# UTX-2022F010.net
KiCad netlist of a schematic drawn in EAGLE
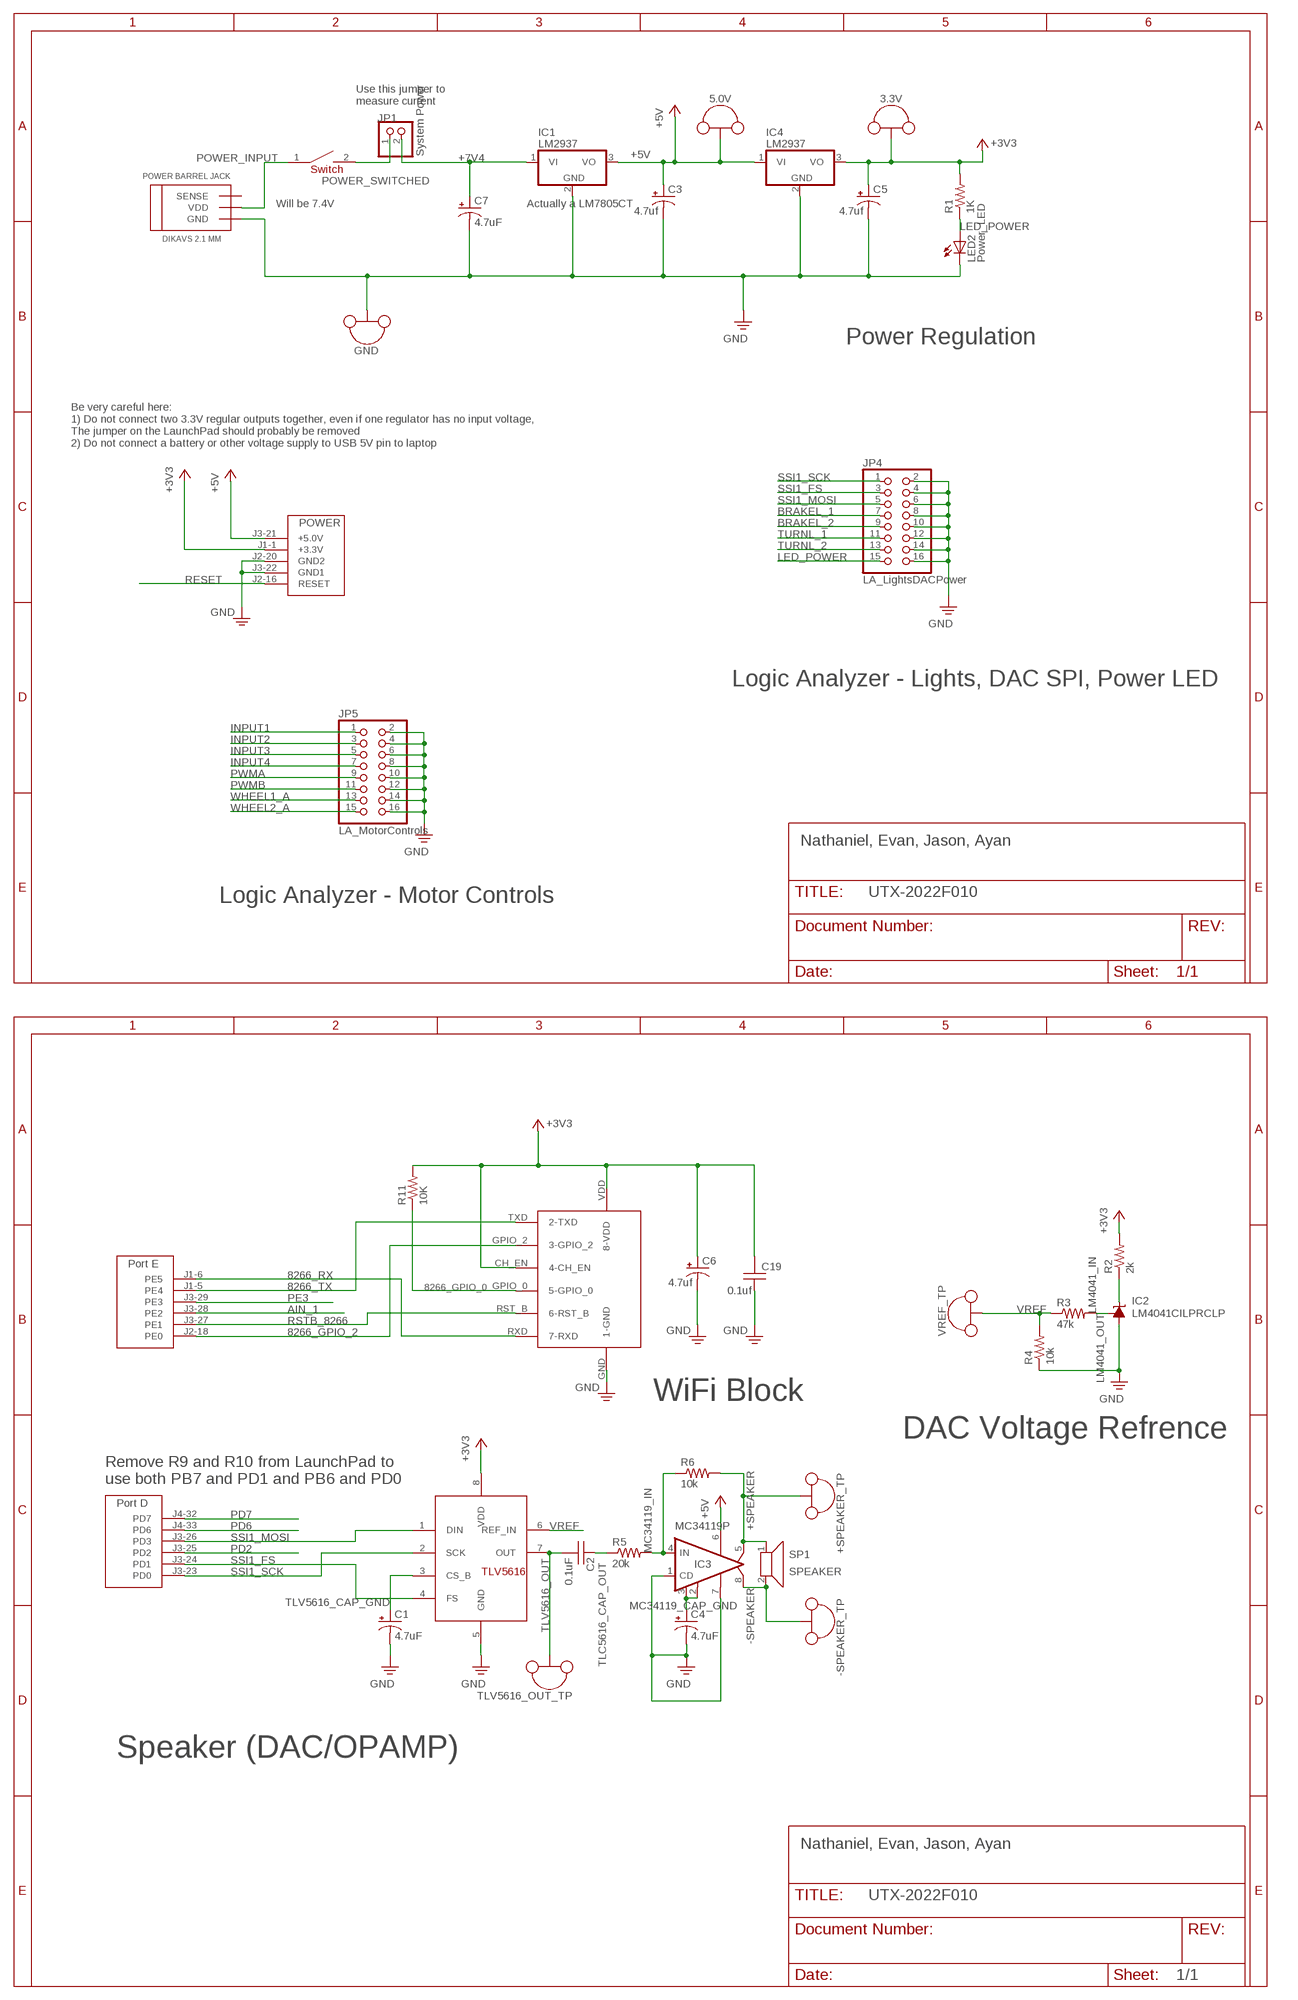
[diagram p0: schematic, sheet 1, part 1 of 2]
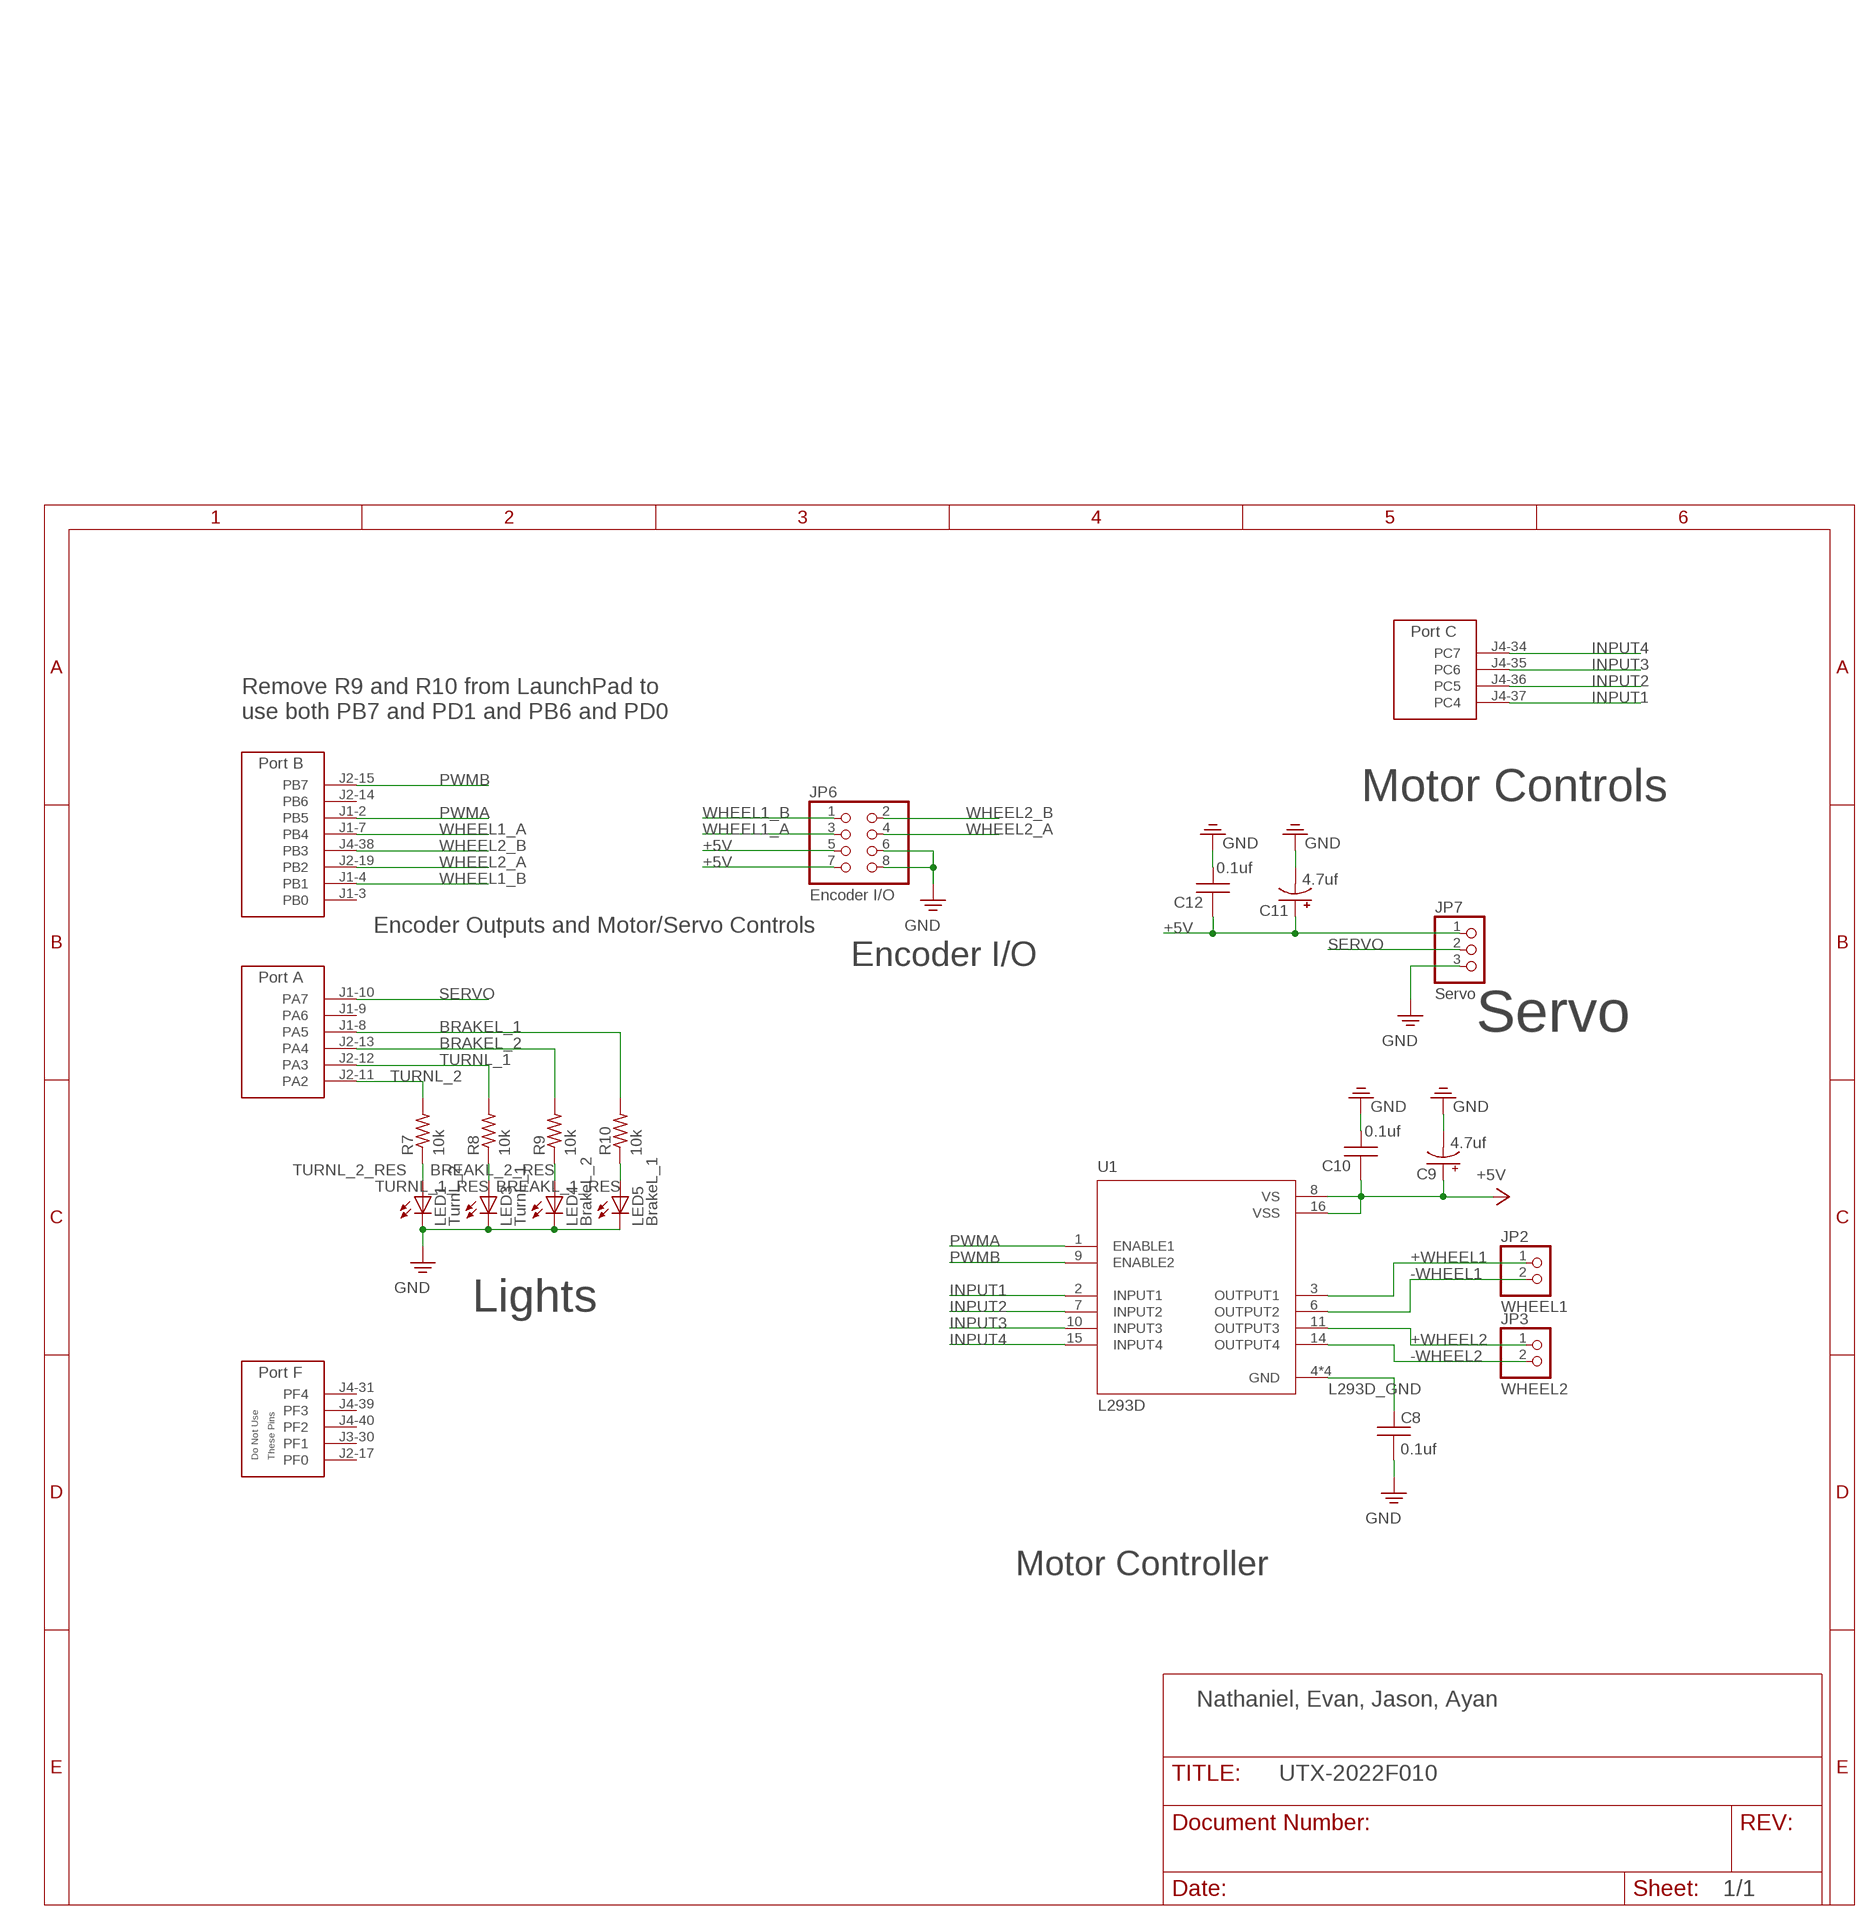
[diagram p1: schematic, sheet 1, part 2 of 2]

(export (version "E")
  (design (tool "Eeschema 10.0.6"))
  (components
    (comp (ref "+SPEAKER_TP")
      (value "TP_LOOP")
      (footprint "eagle-import:TP_LOOP")
      (libsource (lib "eagle-import") (part "TP_LOOP"))
    )
    (comp (ref "-SPEAKER_TP")
      (value "TP_LOOP")
      (footprint "eagle-import:TP_LOOP")
      (libsource (lib "eagle-import") (part "TP_LOOP"))
    )
    (comp (ref "3.3V")
      (value "TP_LOOP")
      (footprint "eagle-import:TP_LOOP")
      (libsource (lib "eagle-import") (part "TP_LOOP"))
    )
    (comp (ref "5.0V")
      (value "TP_LOOP")
      (footprint "eagle-import:TP_LOOP")
      (libsource (lib "eagle-import") (part "TP_LOOP"))
    )
    (comp (ref "C1")
      (value "4.7uF")
      (footprint "eagle-import:CAP200MILPOLARIZED")
      (libsource (lib "eagle-import") (part "CAPACITOR_POLARIZEDE5-6"))
    )
    (comp (ref "C2")
      (value "0.1uF")
      (footprint "eagle-import:CAP100MIL")
      (libsource (lib "eagle-import") (part "CAPACITOR025-024X044"))
    )
    (comp (ref "C3")
      (value "4.7uf")
      (footprint "eagle-import:CAP200MILPOLARIZED")
      (libsource (lib "eagle-import") (part "CAPACITOR_POLARIZEDE5-6"))
    )
    (comp (ref "C4")
      (value "4.7uF")
      (footprint "eagle-import:CAP200MILPOLARIZED")
      (libsource (lib "eagle-import") (part "CAPACITOR_POLARIZEDE5-6"))
    )
    (comp (ref "C5")
      (value "4.7uf")
      (footprint "eagle-import:CAP200MILPOLARIZED")
      (libsource (lib "eagle-import") (part "CAPACITOR_POLARIZEDE5-6"))
    )
    (comp (ref "C6")
      (value "4.7uf")
      (footprint "eagle-import:CAP200MILPOLARIZED")
      (libsource (lib "eagle-import") (part "CAPACITOR_POLARIZEDE5-6"))
    )
    (comp (ref "C7")
      (value "4.7uF")
      (footprint "eagle-import:CAP200MILPOLARIZED")
      (libsource (lib "eagle-import") (part "CAPACITOR_POLARIZEDE5-6"))
    )
    (comp (ref "C8")
      (value "0.1uf")
      (footprint "eagle-import:CAP100MIL")
      (libsource (lib "eagle-import") (part "CAPACITOR025-024X044"))
    )
    (comp (ref "C9")
      (value "4.7uf")
      (footprint "eagle-import:CAP200MILPOLARIZED")
      (libsource (lib "eagle-import") (part "CAPACITOR_POLARIZEDE5-6"))
    )
    (comp (ref "C10")
      (value "0.1uf")
      (footprint "eagle-import:CAP200MIL")
      (libsource (lib "eagle-import") (part "CAPACITOR050-024X044"))
    )
    (comp (ref "C11")
      (value "4.7uf")
      (footprint "eagle-import:CAP200MILPOLARIZED")
      (libsource (lib "eagle-import") (part "CAPACITOR_POLARIZEDE5-6"))
    )
    (comp (ref "C12")
      (value "0.1uf")
      (footprint "eagle-import:CAP200MIL")
      (libsource (lib "eagle-import") (part "CAPACITOR050-024X044"))
    )
    (comp (ref "C19")
      (value "0.1uf")
      (footprint "eagle-import:CAP200MIL")
      (libsource (lib "eagle-import") (part "CAPACITOR050-024X044"))
    )
    (comp (ref "GND")
      (value "TP_LOOP")
      (footprint "eagle-import:TP_LOOP")
      (libsource (lib "eagle-import") (part "TP_LOOP"))
    )
    (comp (ref "IC1")
      (value "LM2937")
      (footprint "eagle-import:TO220")
      (libsource (lib "eagle-import") (part "LM2937"))
    )
    (comp (ref "IC2")
      (value "LM4041CILPRCLP")
      (footprint "eagle-import:LP_O-PBCY-W3")
      (fields (field (name "MPN") "LM4041CILP"))
      (libsource (lib "eagle-import") (part "LM4041CILPRLPC"))
    )
    (comp (ref "IC3")
      (value "MC34119P")
      (footprint "eagle-import:DIL08")
      (libsource (lib "eagle-import") (part "MC34119P"))
    )
    (comp (ref "IC4")
      (value "LM2937")
      (footprint "eagle-import:TO220")
      (libsource (lib "eagle-import") (part "LM2937"))
    )
    (comp (ref "JP1")
      (value "System Power")
      (footprint "eagle-import:1X02")
      (libsource (lib "eagle-import") (part "PINHD-1X2"))
    )
    (comp (ref "JP2")
      (value "WHEEL1")
      (footprint "eagle-import:1X02")
      (libsource (lib "eagle-import") (part "PINHD-1X2"))
    )
    (comp (ref "JP3")
      (value "WHEEL2")
      (footprint "eagle-import:1X02")
      (libsource (lib "eagle-import") (part "PINHD-1X2"))
    )
    (comp (ref "JP4")
      (value "LA_LightsDACPower")
      (footprint "eagle-import:2X08")
      (libsource (lib "eagle-import") (part "PINHD-2X8"))
    )
    (comp (ref "JP5")
      (value "LA_MotorControls")
      (footprint "eagle-import:2X08")
      (libsource (lib "eagle-import") (part "PINHD-2X8"))
    )
    (comp (ref "JP6")
      (value "Encoder I/O")
      (footprint "eagle-import:2X04")
      (libsource (lib "eagle-import") (part "PINHD-2X4"))
    )
    (comp (ref "JP7")
      (value "Servo")
      (footprint "eagle-import:1X03")
      (libsource (lib "eagle-import") (part "PINHD-1X3"))
    )
    (comp (ref "LED1")
      (value "TurnL_2")
      (footprint "eagle-import:LED3MM")
      (libsource (lib "eagle-import") (part "LED3MM"))
    )
    (comp (ref "LED2")
      (value "Power_LED")
      (footprint "eagle-import:LED3MM")
      (libsource (lib "eagle-import") (part "LED3MM"))
    )
    (comp (ref "LED3")
      (value "TurnL_1")
      (footprint "eagle-import:LED3MM")
      (libsource (lib "eagle-import") (part "LED3MM"))
    )
    (comp (ref "LED4")
      (value "BrakeL_2")
      (footprint "eagle-import:LED3MM")
      (libsource (lib "eagle-import") (part "LED3MM"))
    )
    (comp (ref "LED5")
      (value "BrakeL_1")
      (footprint "eagle-import:LED3MM")
      (libsource (lib "eagle-import") (part "LED3MM"))
    )
    (comp (ref "R1")
      (value "1K")
      (footprint "eagle-import:RES200MIL")
      (libsource (lib "eagle-import") (part "RESISTOR0204/5"))
    )
    (comp (ref "R2")
      (value "2k")
      (footprint "eagle-import:RES200MIL")
      (libsource (lib "eagle-import") (part "RESISTOR0204/5"))
    )
    (comp (ref "R3")
      (value "47k")
      (footprint "eagle-import:RES200MIL")
      (libsource (lib "eagle-import") (part "RESISTOR0204/5"))
    )
    (comp (ref "R4")
      (value "10k")
      (footprint "eagle-import:RES200MIL")
      (libsource (lib "eagle-import") (part "RESISTOR0204/5"))
    )
    (comp (ref "R5")
      (value "20k")
      (footprint "eagle-import:RES200MIL")
      (libsource (lib "eagle-import") (part "RESISTOR0204/5"))
    )
    (comp (ref "R6")
      (value "10k")
      (footprint "eagle-import:RES200MIL")
      (libsource (lib "eagle-import") (part "RESISTOR0204/5"))
    )
    (comp (ref "R7")
      (value "10k")
      (footprint "eagle-import:RES200MIL")
      (libsource (lib "eagle-import") (part "RESISTOR0204/5"))
    )
    (comp (ref "R8")
      (value "10k")
      (footprint "eagle-import:RES200MIL")
      (libsource (lib "eagle-import") (part "RESISTOR0204/5"))
    )
    (comp (ref "R9")
      (value "10k")
      (footprint "eagle-import:RES200MIL")
      (libsource (lib "eagle-import") (part "RESISTOR0204/5"))
    )
    (comp (ref "R10")
      (value "10k")
      (footprint "eagle-import:RES200MIL")
      (libsource (lib "eagle-import") (part "RESISTOR0204/5"))
    )
    (comp (ref "R11")
      (value "10K")
      (footprint "eagle-import:RES300MIL")
      (libsource (lib "eagle-import") (part "RESISTOR0204/7"))
    )
    (comp (ref "SP1")
      (value "SPEAKER")
      (footprint "eagle-import:1X02")
      (libsource (lib "eagle-import") (part "SPEAKER"))
    )
    (comp (ref "TLV5616_OUT_TP")
      (value "TP_LOOP")
      (footprint "eagle-import:TP_LOOP")
      (libsource (lib "eagle-import") (part "TP_LOOP"))
    )
    (comp (ref "U$1")
      (value "TLV5616")
      (footprint "eagle-import:DIL08")
      (libsource (lib "eagle-import") (part "TLV5616"))
    )
    (comp (ref "U$2")
      (value "TM4C_BP")
      (footprint "eagle-import:TM4C_BOOSTER_PACK")
      (libsource (lib "eagle-import") (part "TM4C_BP"))
    )
    (comp (ref "U$3")
      (value "ESP_8266")
      (footprint "eagle-import:ESP8266")
      (libsource (lib "eagle-import") (part "ESP_8266"))
    )
    (comp (ref "U$4")
      (value "2.1MM_BARREL_JACK")
      (footprint "eagle-import:2.1M_BARREL_JACK")
      (libsource (lib "eagle-import") (part "2.1MM_BARREL_JACK"))
    )
    (comp (ref "U$6")
      (value "SW_POWER_100MIL")
      (footprint "eagle-import:SW_POWER")
      (libsource (lib "eagle-import") (part "SW_POWER_100MIL"))
    )
    (comp (ref "U1")
      (value "L293D")
      (footprint "eagle-import:DIP880W50P254L2000H510Q16")
      (fields (field (name "MF") "STMicroelectronics"))
      (libsource (lib "eagle-import") (part "L293D"))
    )
    (comp (ref "VREF_TP")
      (value "TP_LOOP")
      (footprint "eagle-import:TP_LOOP")
      (libsource (lib "eagle-import") (part "TP_LOOP"))
    )
  )
  (nets
    (net (code "1") (name "+3V3") (class "Default")
      (node (ref "3.3V") (pin "P$1") (pinfunction "TP_P$1") (pintype "bidirectional"))
      (node (ref "3.3V") (pin "P$2") (pinfunction "TP_P$2") (pintype "bidirectional"))
      (node (ref "C19") (pin "2") (pinfunction "2_2") (pintype "passive"))
      (node (ref "C5") (pin "+") (pinfunction "+_+") (pintype "passive"))
      (node (ref "C6") (pin "+") (pinfunction "+_+") (pintype "passive"))
      (node (ref "IC4") (pin "3") (pinfunction "VO_3") (pintype "passive"))
      (node (ref "R1") (pin "2") (pinfunction "2_2") (pintype "passive"))
      (node (ref "R11") (pin "2") (pinfunction "2_2") (pintype "passive"))
      (node (ref "R2") (pin "2") (pinfunction "2_2") (pintype "passive"))
      (node (ref "U$1") (pin "8") (pinfunction "VDD_8") (pintype "bidirectional"))
      (node (ref "U$2") (pin "J1-1") (pinfunction "+3.3V_J1-1") (pintype "bidirectional"))
      (node (ref "U$3") (pin "CH_EN") (pinfunction "4-CH_EN_CH_EN") (pintype "bidirectional"))
      (node (ref "U$3") (pin "VDD") (pinfunction "8-VDD_VDD") (pintype "bidirectional"))
    )
    (net (code "2") (name "+5V") (class "Default")
      (node (ref "5.0V") (pin "P$1") (pinfunction "TP_P$1") (pintype "bidirectional"))
      (node (ref "5.0V") (pin "P$2") (pinfunction "TP_P$2") (pintype "bidirectional"))
      (node (ref "C10") (pin "2") (pinfunction "2_2") (pintype "passive"))
      (node (ref "C11") (pin "+") (pinfunction "+_+") (pintype "passive"))
      (node (ref "C12") (pin "2") (pinfunction "2_2") (pintype "passive"))
      (node (ref "C3") (pin "+") (pinfunction "+_+") (pintype "passive"))
      (node (ref "C9") (pin "+") (pinfunction "+_+") (pintype "passive"))
      (node (ref "IC1") (pin "3") (pinfunction "VO_3") (pintype "passive"))
      (node (ref "IC3") (pin "6") (pinfunction "VCC_6") (pintype "power_in"))
      (node (ref "IC4") (pin "1") (pinfunction "VI_1") (pintype "input"))
      (node (ref "JP6") (pin "5") (pinfunction "5_5") (pintype "passive"))
      (node (ref "JP6") (pin "7") (pinfunction "7_7") (pintype "passive"))
      (node (ref "JP7") (pin "1") (pinfunction "1_1") (pintype "passive"))
      (node (ref "U$2") (pin "J3-21") (pinfunction "+5.0V_J3-21") (pintype "bidirectional"))
      (node (ref "U1") (pin "16") (pinfunction "VSS_16") (pintype "power_in"))
      (node (ref "U1") (pin "8") (pinfunction "VS_8") (pintype "power_in"))
    )
    (net (code "3") (name "/+7V4") (class "Default")
      (node (ref "C7") (pin "+") (pinfunction "+_+") (pintype "passive"))
      (node (ref "IC1") (pin "1") (pinfunction "VI_1") (pintype "input"))
      (node (ref "JP1") (pin "2") (pinfunction "2_2") (pintype "passive"))
    )
    (net (code "4") (name "/+SPEAKER") (class "Default")
      (node (ref "+SPEAKER_TP") (pin "P$1") (pinfunction "TP_P$1") (pintype "bidirectional"))
      (node (ref "+SPEAKER_TP") (pin "P$2") (pinfunction "TP_P$2") (pintype "bidirectional"))
      (node (ref "IC3") (pin "5") (pinfunction "VO1_5") (pintype "output"))
      (node (ref "R6") (pin "2") (pinfunction "2_2") (pintype "passive"))
      (node (ref "SP1") (pin "1") (pinfunction "1_1") (pintype "passive"))
    )
    (net (code "5") (name "/+WHEEL1") (class "Default")
      (node (ref "JP2") (pin "1") (pinfunction "1_1") (pintype "passive"))
      (node (ref "U1") (pin "3") (pinfunction "OUTPUT1_3") (pintype "output"))
    )
    (net (code "6") (name "/+WHEEL2") (class "Default")
      (node (ref "JP3") (pin "1") (pinfunction "1_1") (pintype "passive"))
      (node (ref "U1") (pin "11") (pinfunction "OUTPUT3_11") (pintype "output"))
    )
    (net (code "7") (name "/-SPEAKER") (class "Default")
      (node (ref "-SPEAKER_TP") (pin "P$1") (pinfunction "TP_P$1") (pintype "bidirectional"))
      (node (ref "-SPEAKER_TP") (pin "P$2") (pinfunction "TP_P$2") (pintype "bidirectional"))
      (node (ref "IC3") (pin "8") (pinfunction "VO2_8") (pintype "output"))
      (node (ref "SP1") (pin "2") (pinfunction "2_2") (pintype "passive"))
    )
    (net (code "8") (name "/-WHEEL1") (class "Default")
      (node (ref "JP2") (pin "2") (pinfunction "2_2") (pintype "passive"))
      (node (ref "U1") (pin "6") (pinfunction "OUTPUT2_6") (pintype "output"))
    )
    (net (code "9") (name "/-WHEEL2") (class "Default")
      (node (ref "JP3") (pin "2") (pinfunction "2_2") (pintype "passive"))
      (node (ref "U1") (pin "14") (pinfunction "OUTPUT4_14") (pintype "output"))
    )
    (net (code "10") (name "/8266_GPIO_0") (class "Default")
      (node (ref "R11") (pin "1") (pinfunction "1_1") (pintype "passive"))
      (node (ref "U$3") (pin "GPIO_0") (pinfunction "5-GPIO_0_GPIO_0") (pintype "bidirectional"))
    )
    (net (code "11") (name "/8266_GPIO_2") (class "Default")
      (node (ref "U$2") (pin "J2-18") (pinfunction "PE0_J2-18") (pintype "bidirectional"))
      (node (ref "U$3") (pin "GPIO_2") (pinfunction "3-GPIO_2_GPIO_2") (pintype "bidirectional"))
    )
    (net (code "12") (name "/8266_RX") (class "Default")
      (node (ref "U$2") (pin "J1-6") (pinfunction "PE5_J1-6") (pintype "bidirectional"))
      (node (ref "U$3") (pin "RXD") (pinfunction "7-RXD_RXD") (pintype "bidirectional"))
    )
    (net (code "13") (name "/8266_TX") (class "Default")
      (node (ref "U$2") (pin "J1-5") (pinfunction "PE4_J1-5") (pintype "bidirectional"))
      (node (ref "U$3") (pin "TXD") (pinfunction "2-TXD_TXD") (pintype "bidirectional"))
    )
    (net (code "14") (name "/AIN_1") (class "Default")
      (node (ref "U$2") (pin "J3-28") (pinfunction "PE2_J3-28") (pintype "bidirectional"))
    )
    (net (code "15") (name "/BRAKEL_1") (class "Default")
      (node (ref "JP4") (pin "7") (pinfunction "7_7") (pintype "passive"))
      (node (ref "R10") (pin "2") (pinfunction "2_2") (pintype "passive"))
      (node (ref "U$2") (pin "J1-8") (pinfunction "PA5_J1-8") (pintype "bidirectional"))
    )
    (net (code "16") (name "/BRAKEL_2") (class "Default")
      (node (ref "JP4") (pin "9") (pinfunction "9_9") (pintype "passive"))
      (node (ref "R9") (pin "2") (pinfunction "2_2") (pintype "passive"))
      (node (ref "U$2") (pin "J2-13") (pinfunction "PA4_J2-13") (pintype "bidirectional"))
    )
    (net (code "17") (name "/BREAKL_1_RES") (class "Default")
      (node (ref "LED5") (pin "A") (pinfunction "A_A") (pintype "passive"))
      (node (ref "R10") (pin "1") (pinfunction "1_1") (pintype "passive"))
    )
    (net (code "18") (name "/BREAKL_2_RES") (class "Default")
      (node (ref "LED4") (pin "A") (pinfunction "A_A") (pintype "passive"))
      (node (ref "R9") (pin "1") (pinfunction "1_1") (pintype "passive"))
    )
    (net (code "19") (name "/INPUT1") (class "Default")
      (node (ref "JP5") (pin "1") (pinfunction "1_1") (pintype "passive"))
      (node (ref "U$2") (pin "J4-37") (pinfunction "PC4_J4-37") (pintype "bidirectional"))
      (node (ref "U1") (pin "2") (pinfunction "INPUT1_2") (pintype "input"))
    )
    (net (code "20") (name "/INPUT2") (class "Default")
      (node (ref "JP5") (pin "3") (pinfunction "3_3") (pintype "passive"))
      (node (ref "U$2") (pin "J4-36") (pinfunction "PC5_J4-36") (pintype "bidirectional"))
      (node (ref "U1") (pin "7") (pinfunction "INPUT2_7") (pintype "input"))
    )
    (net (code "21") (name "/INPUT3") (class "Default")
      (node (ref "JP5") (pin "5") (pinfunction "5_5") (pintype "passive"))
      (node (ref "U$2") (pin "J4-35") (pinfunction "PC6_J4-35") (pintype "bidirectional"))
      (node (ref "U1") (pin "10") (pinfunction "INPUT3_10") (pintype "input"))
    )
    (net (code "22") (name "/INPUT4") (class "Default")
      (node (ref "JP5") (pin "7") (pinfunction "7_7") (pintype "passive"))
      (node (ref "U$2") (pin "J4-34") (pinfunction "PC7_J4-34") (pintype "bidirectional"))
      (node (ref "U1") (pin "15") (pinfunction "INPUT4_15") (pintype "input"))
    )
    (net (code "23") (name "/L293D_GND") (class "Default")
      (node (ref "C8") (pin "1") (pinfunction "1_1") (pintype "passive"))
      (node (ref "U1") (pin "12") (pinfunction "GND_12") (pintype "power_in"))
      (node (ref "U1") (pin "13") (pinfunction "GND_13") (pintype "power_in"))
      (node (ref "U1") (pin "4") (pinfunction "GND_4") (pintype "power_in"))
      (node (ref "U1") (pin "5") (pinfunction "GND_5") (pintype "power_in"))
    )
    (net (code "24") (name "/LED_POWER") (class "Default")
      (node (ref "JP4") (pin "15") (pinfunction "15_15") (pintype "passive"))
      (node (ref "LED2") (pin "A") (pinfunction "A_A") (pintype "passive"))
      (node (ref "R1") (pin "1") (pinfunction "1_1") (pintype "passive"))
    )
    (net (code "25") (name "/LM4041_IN") (class "Default")
      (node (ref "IC2") (pin "2") (pinfunction "C_2") (pintype "passive"))
      (node (ref "R2") (pin "1") (pinfunction "1_1") (pintype "passive"))
    )
    (net (code "26") (name "/LM4041_OUT") (class "Default")
      (node (ref "IC2") (pin "1") (pinfunction "FB_1") (pintype "passive"))
      (node (ref "R3") (pin "2") (pinfunction "2_2") (pintype "passive"))
    )
    (net (code "27") (name "/MC34119_CAP_GND") (class "Default")
      (node (ref "C4") (pin "+") (pinfunction "+_+") (pintype "passive"))
      (node (ref "IC3") (pin "2") (pinfunction "FC2_2") (pintype "passive"))
      (node (ref "IC3") (pin "3") (pinfunction "FC1_3") (pintype "passive"))
    )
    (net (code "28") (name "/MC34119_IN") (class "Default")
      (node (ref "IC3") (pin "4") (pinfunction "IN_4") (pintype "input"))
      (node (ref "R5") (pin "2") (pinfunction "2_2") (pintype "passive"))
      (node (ref "R6") (pin "1") (pinfunction "1_1") (pintype "passive"))
    )
    (net (code "29") (name "/PD2") (class "Default")
      (node (ref "U$2") (pin "J3-25") (pinfunction "PD2_J3-25") (pintype "bidirectional"))
    )
    (net (code "30") (name "/PD6") (class "Default")
      (node (ref "U$2") (pin "J4-33") (pinfunction "PD6_J4-33") (pintype "bidirectional"))
    )
    (net (code "31") (name "/PD7") (class "Default")
      (node (ref "U$2") (pin "J4-32") (pinfunction "PD7_J4-32") (pintype "bidirectional"))
    )
    (net (code "32") (name "/PE3") (class "Default")
      (node (ref "U$2") (pin "J3-29") (pinfunction "PE3_J3-29") (pintype "bidirectional"))
    )
    (net (code "33") (name "/POWER_INPUT") (class "Default")
      (node (ref "U$4") (pin "VDD") (pinfunction "VDD_VDD") (pintype "bidirectional"))
      (node (ref "U$6") (pin "1") (pinfunction "P$1_1") (pintype "bidirectional"))
    )
    (net (code "34") (name "/POWER_SWITCHED") (class "Default")
      (node (ref "JP1") (pin "1") (pinfunction "1_1") (pintype "passive"))
      (node (ref "U$6") (pin "2") (pinfunction "P$2_2") (pintype "bidirectional"))
    )
    (net (code "35") (name "/PWMA") (class "Default")
      (node (ref "JP5") (pin "9") (pinfunction "9_9") (pintype "passive"))
      (node (ref "U$2") (pin "J1-2") (pinfunction "PB5_J1-2") (pintype "bidirectional"))
      (node (ref "U1") (pin "1") (pinfunction "ENABLE1_1") (pintype "input"))
    )
    (net (code "36") (name "/PWMB") (class "Default")
      (node (ref "JP5") (pin "11") (pinfunction "11_11") (pintype "passive"))
      (node (ref "U$2") (pin "J2-15") (pinfunction "PB7_J2-15") (pintype "bidirectional"))
      (node (ref "U1") (pin "9") (pinfunction "ENABLE2_9") (pintype "input"))
    )
    (net (code "37") (name "/RESET") (class "Default")
      (node (ref "U$2") (pin "J2-16") (pinfunction "RESET_J2-16") (pintype "bidirectional"))
    )
    (net (code "38") (name "/RSTB_8266") (class "Default")
      (node (ref "U$2") (pin "J3-27") (pinfunction "PE1_J3-27") (pintype "bidirectional"))
      (node (ref "U$3") (pin "RST_B") (pinfunction "6-RST_B_RST_B") (pintype "bidirectional"))
    )
    (net (code "39") (name "/SERVO") (class "Default")
      (node (ref "JP7") (pin "2") (pinfunction "2_2") (pintype "passive"))
      (node (ref "U$2") (pin "J1-10") (pinfunction "PA7_J1-10") (pintype "bidirectional"))
    )
    (net (code "40") (name "/SSI1_FS") (class "Default")
      (node (ref "JP4") (pin "3") (pinfunction "3_3") (pintype "passive"))
      (node (ref "U$1") (pin "4") (pinfunction "FS_4") (pintype "bidirectional"))
      (node (ref "U$2") (pin "J3-24") (pinfunction "PD1_J3-24") (pintype "bidirectional"))
    )
    (net (code "41") (name "/SSI1_MOSI") (class "Default")
      (node (ref "JP4") (pin "5") (pinfunction "5_5") (pintype "passive"))
      (node (ref "U$1") (pin "1") (pinfunction "DIN_1") (pintype "bidirectional"))
      (node (ref "U$2") (pin "J3-26") (pinfunction "PD3_J3-26") (pintype "bidirectional"))
    )
    (net (code "42") (name "/SSI1_SCK") (class "Default")
      (node (ref "JP4") (pin "1") (pinfunction "1_1") (pintype "passive"))
      (node (ref "U$1") (pin "2") (pinfunction "SCK_2") (pintype "bidirectional"))
      (node (ref "U$2") (pin "J3-23") (pinfunction "PD0_J3-23") (pintype "bidirectional"))
    )
    (net (code "43") (name "/TLC5616_CAP_OUT") (class "Default")
      (node (ref "C2") (pin "1") (pinfunction "1_1") (pintype "passive"))
      (node (ref "R5") (pin "1") (pinfunction "1_1") (pintype "passive"))
    )
    (net (code "44") (name "/TLV5616_CAP_GND") (class "Default")
      (node (ref "C1") (pin "+") (pinfunction "+_+") (pintype "passive"))
      (node (ref "U$1") (pin "3") (pinfunction "CS_B_3") (pintype "bidirectional"))
    )
    (net (code "45") (name "/TLV5616_OUT") (class "Default")
      (node (ref "C2") (pin "2") (pinfunction "2_2") (pintype "passive"))
      (node (ref "TLV5616_OUT_TP") (pin "P$1") (pinfunction "TP_P$1") (pintype "bidirectional"))
      (node (ref "TLV5616_OUT_TP") (pin "P$2") (pinfunction "TP_P$2") (pintype "bidirectional"))
      (node (ref "U$1") (pin "7") (pinfunction "OUT_7") (pintype "bidirectional"))
    )
    (net (code "46") (name "/TURNL_1") (class "Default")
      (node (ref "JP4") (pin "11") (pinfunction "11_11") (pintype "passive"))
      (node (ref "R8") (pin "2") (pinfunction "2_2") (pintype "passive"))
      (node (ref "U$2") (pin "J2-12") (pinfunction "PA3_J2-12") (pintype "bidirectional"))
    )
    (net (code "47") (name "/TURNL_1_RES") (class "Default")
      (node (ref "LED3") (pin "A") (pinfunction "A_A") (pintype "passive"))
      (node (ref "R8") (pin "1") (pinfunction "1_1") (pintype "passive"))
    )
    (net (code "48") (name "/TURNL_2") (class "Default")
      (node (ref "JP4") (pin "13") (pinfunction "13_13") (pintype "passive"))
      (node (ref "R7") (pin "2") (pinfunction "2_2") (pintype "passive"))
      (node (ref "U$2") (pin "J2-11") (pinfunction "PA2_J2-11") (pintype "bidirectional"))
    )
    (net (code "49") (name "/TURNL_2_RES") (class "Default")
      (node (ref "LED1") (pin "A") (pinfunction "A_A") (pintype "passive"))
      (node (ref "R7") (pin "1") (pinfunction "1_1") (pintype "passive"))
    )
    (net (code "50") (name "/VREF") (class "Default")
      (node (ref "R3") (pin "1") (pinfunction "1_1") (pintype "passive"))
      (node (ref "R4") (pin "2") (pinfunction "2_2") (pintype "passive"))
      (node (ref "U$1") (pin "6") (pinfunction "REF_IN_6") (pintype "bidirectional"))
      (node (ref "VREF_TP") (pin "P$1") (pinfunction "TP_P$1") (pintype "bidirectional"))
      (node (ref "VREF_TP") (pin "P$2") (pinfunction "TP_P$2") (pintype "bidirectional"))
    )
    (net (code "51") (name "/WHEEL1_A") (class "Default")
      (node (ref "JP5") (pin "13") (pinfunction "13_13") (pintype "passive"))
      (node (ref "JP6") (pin "3") (pinfunction "3_3") (pintype "passive"))
      (node (ref "U$2") (pin "J1-7") (pinfunction "PB4_J1-7") (pintype "bidirectional"))
    )
    (net (code "52") (name "/WHEEL1_B") (class "Default")
      (node (ref "JP6") (pin "1") (pinfunction "1_1") (pintype "passive"))
      (node (ref "U$2") (pin "J1-4") (pinfunction "PB1_J1-4") (pintype "bidirectional"))
    )
    (net (code "53") (name "/WHEEL2_A") (class "Default")
      (node (ref "JP5") (pin "15") (pinfunction "15_15") (pintype "passive"))
      (node (ref "JP6") (pin "4") (pinfunction "4_4") (pintype "passive"))
      (node (ref "U$2") (pin "J2-19") (pinfunction "PB2_J2-19") (pintype "bidirectional"))
    )
    (net (code "54") (name "/WHEEL2_B") (class "Default")
      (node (ref "JP6") (pin "2") (pinfunction "2_2") (pintype "passive"))
      (node (ref "U$2") (pin "J4-38") (pinfunction "PB3_J4-38") (pintype "bidirectional"))
    )
    (net (code "55") (name "GND") (class "Default")
      (node (ref "C1") (pin "-") (pinfunction "-_-") (pintype "passive"))
      (node (ref "C10") (pin "1") (pinfunction "1_1") (pintype "passive"))
      (node (ref "C11") (pin "-") (pinfunction "-_-") (pintype "passive"))
      (node (ref "C12") (pin "1") (pinfunction "1_1") (pintype "passive"))
      (node (ref "C19") (pin "1") (pinfunction "1_1") (pintype "passive"))
      (node (ref "C3") (pin "-") (pinfunction "-_-") (pintype "passive"))
      (node (ref "C4") (pin "-") (pinfunction "-_-") (pintype "passive"))
      (node (ref "C5") (pin "-") (pinfunction "-_-") (pintype "passive"))
      (node (ref "C6") (pin "-") (pinfunction "-_-") (pintype "passive"))
      (node (ref "C7") (pin "-") (pinfunction "-_-") (pintype "passive"))
      (node (ref "C8") (pin "2") (pinfunction "2_2") (pintype "passive"))
      (node (ref "C9") (pin "-") (pinfunction "-_-") (pintype "passive"))
      (node (ref "GND") (pin "P$1") (pinfunction "TP_P$1") (pintype "bidirectional"))
      (node (ref "GND") (pin "P$2") (pinfunction "TP_P$2") (pintype "bidirectional"))
      (node (ref "IC1") (pin "2") (pinfunction "GND_2") (pintype "passive"))
      (node (ref "IC2") (pin "3") (pinfunction "A_3") (pintype "passive"))
      (node (ref "IC3") (pin "1") (pinfunction "CD_1") (pintype "passive"))
      (node (ref "IC3") (pin "7") (pinfunction "GND_7") (pintype "power_in"))
      (node (ref "IC4") (pin "2") (pinfunction "GND_2") (pintype "passive"))
      (node (ref "JP4") (pin "10") (pinfunction "10_10") (pintype "passive"))
      (node (ref "JP4") (pin "12") (pinfunction "12_12") (pintype "passive"))
      (node (ref "JP4") (pin "14") (pinfunction "14_14") (pintype "passive"))
      (node (ref "JP4") (pin "16") (pinfunction "16_16") (pintype "passive"))
      (node (ref "JP4") (pin "2") (pinfunction "2_2") (pintype "passive"))
      (node (ref "JP4") (pin "4") (pinfunction "4_4") (pintype "passive"))
      (node (ref "JP4") (pin "6") (pinfunction "6_6") (pintype "passive"))
      (node (ref "JP4") (pin "8") (pinfunction "8_8") (pintype "passive"))
      (node (ref "JP5") (pin "10") (pinfunction "10_10") (pintype "passive"))
      (node (ref "JP5") (pin "12") (pinfunction "12_12") (pintype "passive"))
      (node (ref "JP5") (pin "14") (pinfunction "14_14") (pintype "passive"))
      (node (ref "JP5") (pin "16") (pinfunction "16_16") (pintype "passive"))
      (node (ref "JP5") (pin "2") (pinfunction "2_2") (pintype "passive"))
      (node (ref "JP5") (pin "4") (pinfunction "4_4") (pintype "passive"))
      (node (ref "JP5") (pin "6") (pinfunction "6_6") (pintype "passive"))
      (node (ref "JP5") (pin "8") (pinfunction "8_8") (pintype "passive"))
      (node (ref "JP6") (pin "6") (pinfunction "6_6") (pintype "passive"))
      (node (ref "JP6") (pin "8") (pinfunction "8_8") (pintype "passive"))
      (node (ref "JP7") (pin "3") (pinfunction "3_3") (pintype "passive"))
      (node (ref "LED1") (pin "K") (pinfunction "C_K") (pintype "passive"))
      (node (ref "LED2") (pin "K") (pinfunction "C_K") (pintype "passive"))
      (node (ref "LED3") (pin "K") (pinfunction "C_K") (pintype "passive"))
      (node (ref "LED4") (pin "K") (pinfunction "C_K") (pintype "passive"))
      (node (ref "LED5") (pin "K") (pinfunction "C_K") (pintype "passive"))
      (node (ref "R4") (pin "1") (pinfunction "1_1") (pintype "passive"))
      (node (ref "U$1") (pin "5") (pinfunction "GND_5") (pintype "bidirectional"))
      (node (ref "U$2") (pin "J2-20") (pinfunction "GND2_J2-20") (pintype "bidirectional"))
      (node (ref "U$2") (pin "J3-22") (pinfunction "GND1_J3-22") (pintype "bidirectional"))
      (node (ref "U$3") (pin "GND") (pinfunction "1-GND_GND") (pintype "bidirectional"))
      (node (ref "U$4") (pin "GND") (pinfunction "GND_GND") (pintype "bidirectional"))
    )
    (net (code "56") (name "unconnected-(U$2A-PA6-PadJ1-9)") (class "Default")
      (node (ref "U$2") (pin "J1-9") (pinfunction "PA6_J1-9") (pintype "bidirectional"))
    )
    (net (code "57") (name "unconnected-(U$2B-PB0-PadJ1-3)") (class "Default")
      (node (ref "U$2") (pin "J1-3") (pinfunction "PB0_J1-3") (pintype "bidirectional"))
    )
    (net (code "58") (name "unconnected-(U$2B-PB6-PadJ2-14)") (class "Default")
      (node (ref "U$2") (pin "J2-14") (pinfunction "PB6_J2-14") (pintype "bidirectional"))
    )
    (net (code "59") (name "unconnected-(U$2F-PF0-PadJ2-17)") (class "Default")
      (node (ref "U$2") (pin "J2-17") (pinfunction "PF0_J2-17") (pintype "bidirectional"))
    )
    (net (code "60") (name "unconnected-(U$2F-PF1-PadJ3-30)") (class "Default")
      (node (ref "U$2") (pin "J3-30") (pinfunction "PF1_J3-30") (pintype "bidirectional"))
    )
    (net (code "61") (name "unconnected-(U$2F-PF2-PadJ4-40)") (class "Default")
      (node (ref "U$2") (pin "J4-40") (pinfunction "PF2_J4-40") (pintype "bidirectional"))
    )
    (net (code "62") (name "unconnected-(U$2F-PF3-PadJ4-39)") (class "Default")
      (node (ref "U$2") (pin "J4-39") (pinfunction "PF3_J4-39") (pintype "bidirectional"))
    )
    (net (code "63") (name "unconnected-(U$2F-PF4-PadJ4-31)") (class "Default")
      (node (ref "U$2") (pin "J4-31") (pinfunction "PF4_J4-31") (pintype "bidirectional"))
    )
    (net (code "64") (name "unconnected-(U$4-PadSENSE)") (class "Default")
      (node (ref "U$4") (pin "SENSE") (pinfunction "SENSE_SENSE") (pintype "bidirectional"))
    )
  )
)
